# Arduino_S3v3_R2_ftdi.net
KiCad netlist of a schematic drawn in EAGLE
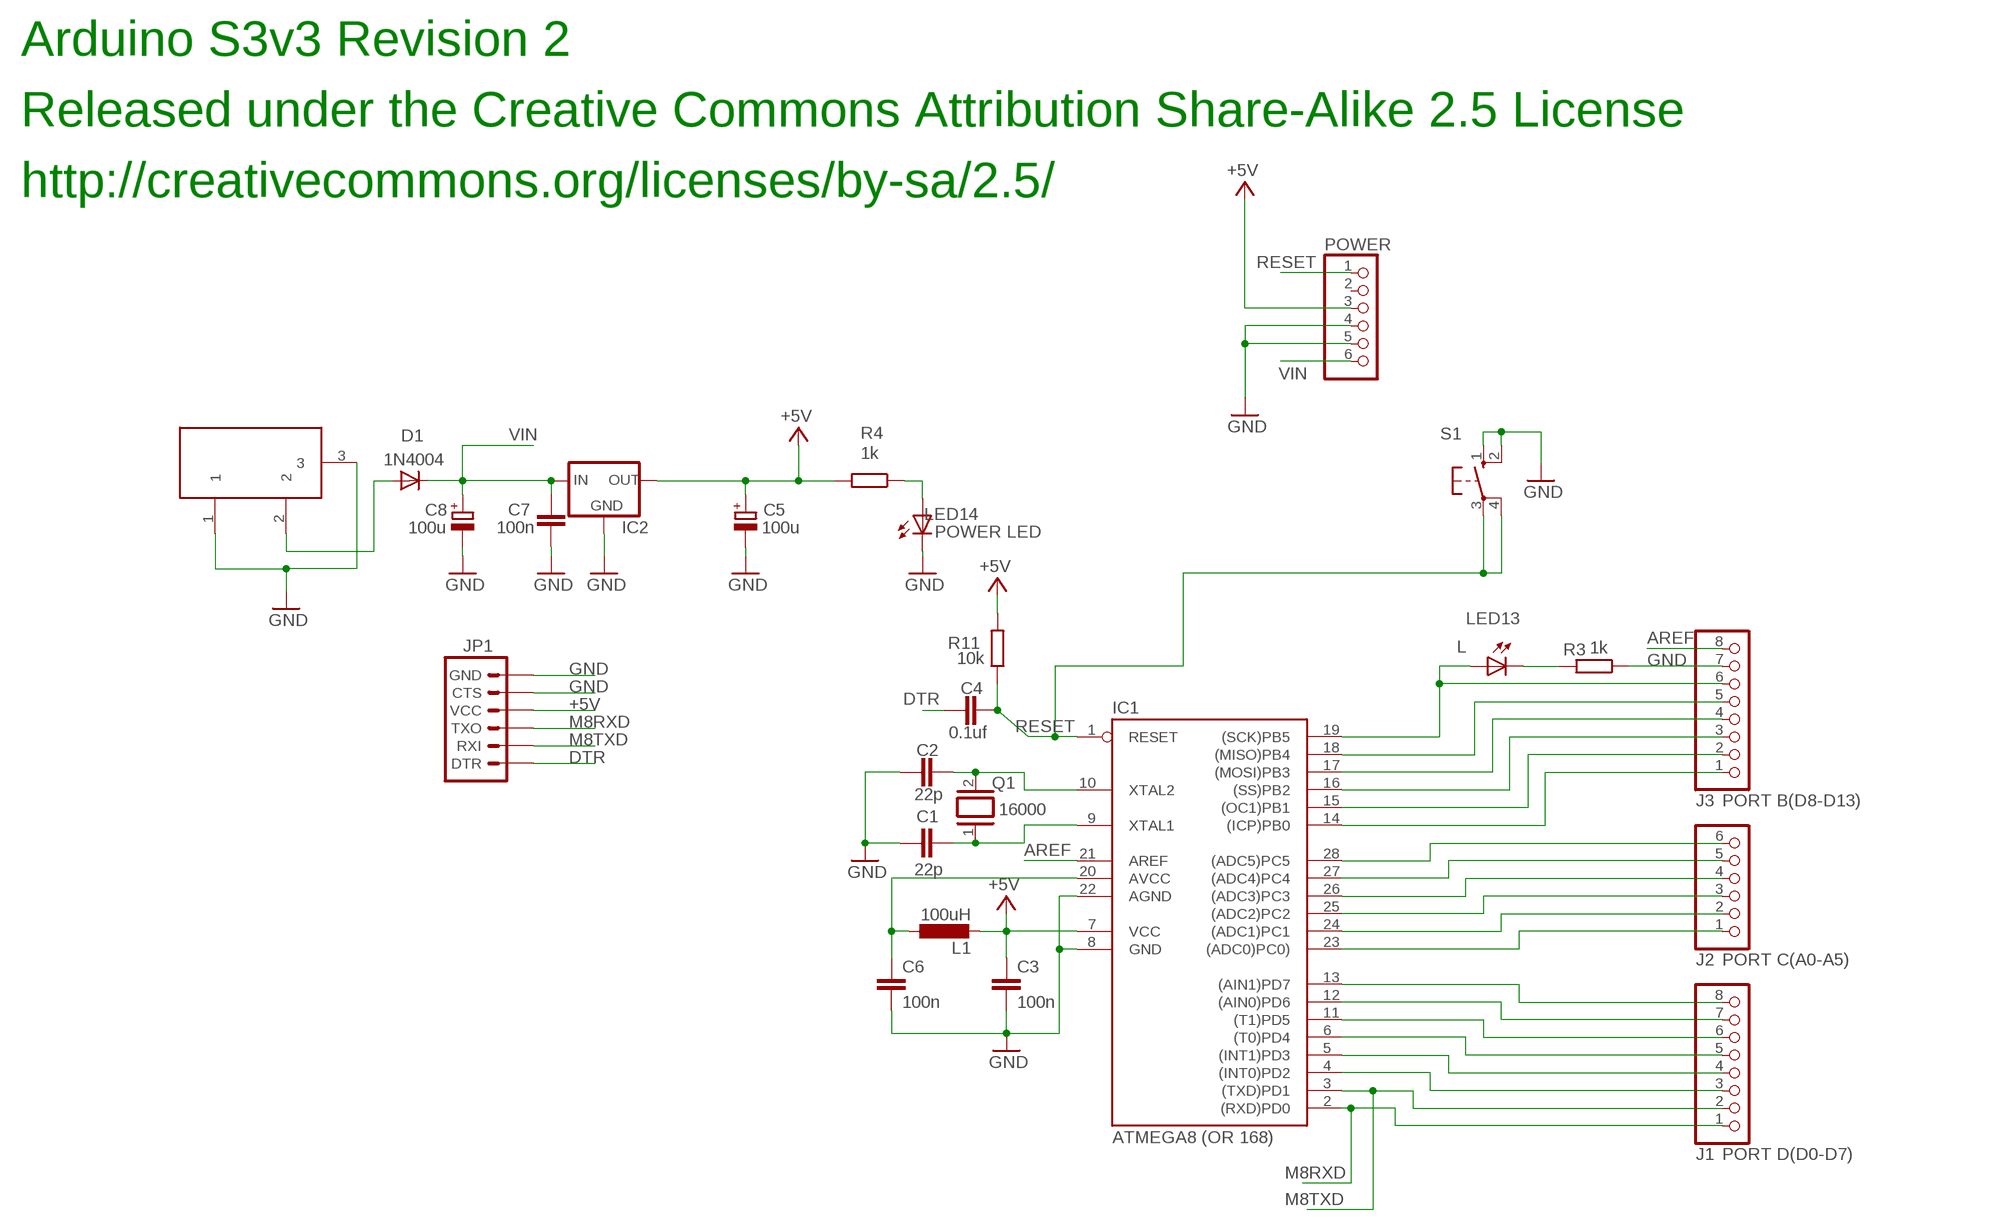
[diagram p0: schematic, sheet 1]

(export (version "E")
  (design (tool "Eeschema 10.0.6"))
  (components
    (comp (ref "C1")
      (value "22p")
      (footprint "eagle-import:C050-025X075")
      (libsource (lib "eagle-import") (part "C-EU050-025X075"))
    )
    (comp (ref "C2")
      (value "22p")
      (footprint "eagle-import:C050-025X075")
      (libsource (lib "eagle-import") (part "C-EU050-025X075"))
    )
    (comp (ref "C3")
      (value "100n")
      (footprint "eagle-import:C050-025X075")
      (libsource (lib "eagle-import") (part "C-EU050-025X075"))
    )
    (comp (ref "C4")
      (value "0.1uf")
      (footprint "eagle-import:C050-025X075")
      (libsource (lib "eagle-import") (part "C-EU050-025X075"))
    )
    (comp (ref "C5")
      (value "100u")
      (footprint "eagle-import:E3,5-8")
      (libsource (lib "eagle-import") (part "CPOL-EUE3.5-8"))
    )
    (comp (ref "C6")
      (value "100n")
      (footprint "eagle-import:C050-025X075")
      (libsource (lib "eagle-import") (part "C-EU050-025X075"))
    )
    (comp (ref "C7")
      (value "100n")
      (footprint "eagle-import:C050-025X075")
      (libsource (lib "eagle-import") (part "C-EU050-025X075"))
    )
    (comp (ref "C8")
      (value "100u")
      (footprint "eagle-import:E3,5-8")
      (libsource (lib "eagle-import") (part "CPOL-EUE3.5-8"))
    )
    (comp (ref "D1")
      (value "1N4004")
      (footprint "eagle-import:DO41-10")
      (libsource (lib "eagle-import") (part "1N4004"))
    )
    (comp (ref "DC1")
      (value "DC21MMX")
      (footprint "eagle-import:DC-21MM")
      (libsource (lib "eagle-import") (part "DC21MMX"))
    )
    (comp (ref "IC1")
      (value "ATMEGA8 (OR 168)")
      (footprint "eagle-import:DIL28-3")
      (libsource (lib "eagle-import") (part "AT90S4433P"))
    )
    (comp (ref "IC2")
      (value "78XXL")
      (footprint "eagle-import:78XXL")
      (libsource (lib "eagle-import") (part "78XXL"))
    )
    (comp (ref "J1")
      (value "PORT D(D0-D7)")
      (footprint "eagle-import:1X08")
      (libsource (lib "eagle-import") (part "PINHD-1X8"))
    )
    (comp (ref "J2")
      (value "PORT C(A0-A5)")
      (footprint "eagle-import:1X06")
      (libsource (lib "eagle-import") (part "PINHD-1X6"))
    )
    (comp (ref "J3")
      (value "PORT B(D8-D13)")
      (footprint "eagle-import:1X08")
      (libsource (lib "eagle-import") (part "PINHD-1X8"))
    )
    (comp (ref "JP1")
      (value "ARDUINO_SERIAL_PROGRAMLONGPADS")
      (footprint "eagle-import:1X06_LONGPADS")
      (libsource (lib "eagle-import") (part "ARDUINO_SERIAL_PROGRAMLONGPADS"))
    )
    (comp (ref "L1")
      (value "100uH")
      (footprint "eagle-import:0207_10@1")
      (libsource (lib "eagle-import") (part "L-EU0207/10"))
    )
    (comp (ref "LED13")
      (value "L")
      (footprint "eagle-import:LED3MM")
      (libsource (lib "eagle-import") (part "LED3MM"))
    )
    (comp (ref "LED14")
      (value "POWER LED")
      (footprint "eagle-import:LED3MM")
      (libsource (lib "eagle-import") (part "LED3MM"))
    )
    (comp (ref "POWER")
      (value "PINHD-1X6")
      (footprint "eagle-import:1X06")
      (libsource (lib "eagle-import") (part "PINHD-1X6"))
    )
    (comp (ref "Q1")
      (value "16000")
      (footprint "eagle-import:Q")
      (libsource (lib "eagle-import") (part "XTAL"))
    )
    (comp (ref "R3")
      (value "1k")
      (footprint "eagle-import:0207_10")
      (libsource (lib "eagle-import") (part "R-EU_0207/10"))
    )
    (comp (ref "R4")
      (value "1k")
      (footprint "eagle-import:0207_10")
      (libsource (lib "eagle-import") (part "R-EU_0207/10"))
    )
    (comp (ref "R11")
      (value "10k")
      (footprint "eagle-import:0207_10")
      (libsource (lib "eagle-import") (part "R-EU_0207/10"))
    )
    (comp (ref "S1")
      (value "10-XX")
      (footprint "eagle-import:B3F-10XX")
      (libsource (lib "eagle-import") (part "10-XX"))
    )
  )
  (nets
    (net (code "1") (name "+5V") (class "Default")
      (node (ref "C3") (pin "1") (pinfunction "1_1") (pintype "passive"))
      (node (ref "C5") (pin "+") (pinfunction "+_+") (pintype "passive"))
      (node (ref "IC1") (pin "7") (pinfunction "VCC_7") (pintype "power_in"))
      (node (ref "IC2") (pin "OUT") (pinfunction "OUT_OUT") (pintype "passive"))
      (node (ref "JP1") (pin "4") (pinfunction "VCC_4") (pintype "passive"))
      (node (ref "L1") (pin "2") (pinfunction "2_2") (pintype "passive"))
      (node (ref "POWER") (pin "3") (pinfunction "3_3") (pintype "passive"))
      (node (ref "R11") (pin "2") (pinfunction "2_2") (pintype "passive"))
      (node (ref "R4") (pin "2") (pinfunction "2_2") (pintype "passive"))
    )
    (net (code "2") (name "/AREF") (class "Default")
      (node (ref "IC1") (pin "21") (pinfunction "AREF_21") (pintype "power_in"))
      (node (ref "J3") (pin "8") (pinfunction "8_8") (pintype "passive"))
    )
    (net (code "3") (name "/DTR") (class "Default")
      (node (ref "C4") (pin "1") (pinfunction "1_1") (pintype "passive"))
      (node (ref "JP1") (pin "1") (pinfunction "DTR_1") (pintype "passive"))
    )
    (net (code "4") (name "/M8RXD") (class "Default")
      (node (ref "IC1") (pin "2") (pinfunction "(RXD)PD0_2") (pintype "bidirectional"))
      (node (ref "J1") (pin "1") (pinfunction "1_1") (pintype "passive"))
      (node (ref "JP1") (pin "3") (pinfunction "TXO_3") (pintype "passive"))
    )
    (net (code "5") (name "/M8TXD") (class "Default")
      (node (ref "IC1") (pin "3") (pinfunction "(TXD)PD1_3") (pintype "bidirectional"))
      (node (ref "J1") (pin "2") (pinfunction "2_2") (pintype "passive"))
      (node (ref "JP1") (pin "2") (pinfunction "RXI_2") (pintype "passive"))
    )
    (net (code "6") (name "/RESET") (class "Default")
      (node (ref "C4") (pin "2") (pinfunction "2_2") (pintype "passive"))
      (node (ref "IC1") (pin "1") (pinfunction "RESET_1") (pintype "input"))
      (node (ref "POWER") (pin "1") (pinfunction "1_1") (pintype "passive"))
      (node (ref "R11") (pin "1") (pinfunction "1_1") (pintype "passive"))
      (node (ref "S1") (pin "3") (pinfunction "P_3") (pintype "passive"))
      (node (ref "S1") (pin "4") (pinfunction "P1_4") (pintype "passive"))
    )
    (net (code "7") (name "/VIN") (class "Default")
      (node (ref "C7") (pin "2") (pinfunction "2_2") (pintype "passive"))
      (node (ref "C8") (pin "+") (pinfunction "+_+") (pintype "passive"))
      (node (ref "D1") (pin "C") (pinfunction "C_C") (pintype "passive"))
      (node (ref "IC2") (pin "IN") (pinfunction "IN_IN") (pintype "input"))
      (node (ref "POWER") (pin "6") (pinfunction "6_6") (pintype "passive"))
    )
    (net (code "8") (name "GND") (class "Default")
      (node (ref "C1") (pin "1") (pinfunction "1_1") (pintype "passive"))
      (node (ref "C2") (pin "1") (pinfunction "1_1") (pintype "passive"))
      (node (ref "C3") (pin "2") (pinfunction "2_2") (pintype "passive"))
      (node (ref "C5") (pin "-") (pinfunction "-_-") (pintype "passive"))
      (node (ref "C6") (pin "2") (pinfunction "2_2") (pintype "passive"))
      (node (ref "C7") (pin "1") (pinfunction "1_1") (pintype "passive"))
      (node (ref "C8") (pin "-") (pinfunction "-_-") (pintype "passive"))
      (node (ref "DC1") (pin "1") (pinfunction "1_1") (pintype "power_in"))
      (node (ref "DC1") (pin "3") (pinfunction "3_3") (pintype "power_in"))
      (node (ref "IC1") (pin "22") (pinfunction "AGND_22") (pintype "power_in"))
      (node (ref "IC1") (pin "8") (pinfunction "GND_8") (pintype "power_in"))
      (node (ref "IC2") (pin "GND") (pinfunction "GND_GND") (pintype "input"))
      (node (ref "J3") (pin "7") (pinfunction "7_7") (pintype "passive"))
      (node (ref "JP1") (pin "5") (pinfunction "CTS_5") (pintype "passive"))
      (node (ref "JP1") (pin "6") (pinfunction "GND_6") (pintype "passive"))
      (node (ref "LED14") (pin "K") (pinfunction "C_K") (pintype "passive"))
      (node (ref "POWER") (pin "4") (pinfunction "4_4") (pintype "passive"))
      (node (ref "POWER") (pin "5") (pinfunction "5_5") (pintype "passive"))
      (node (ref "R3") (pin "1") (pinfunction "1_1") (pintype "passive"))
      (node (ref "S1") (pin "1") (pinfunction "S_1") (pintype "passive"))
      (node (ref "S1") (pin "2") (pinfunction "S1_2") (pintype "passive"))
    )
    (net (code "9") (name "Net-(D1-PadA)") (class "Default")
      (node (ref "D1") (pin "A") (pinfunction "A_A") (pintype "passive"))
      (node (ref "DC1") (pin "2") (pinfunction "2_2") (pintype "power_in"))
    )
    (net (code "10") (name "Net-(IC1-(ADC0)PC0))") (class "Default")
      (node (ref "IC1") (pin "23") (pinfunction "(ADC0)PC0)_23") (pintype "bidirectional"))
      (node (ref "J2") (pin "1") (pinfunction "1_1") (pintype "passive"))
    )
    (net (code "11") (name "Net-(IC1-(ADC1)PC1)") (class "Default")
      (node (ref "IC1") (pin "24") (pinfunction "(ADC1)PC1_24") (pintype "bidirectional"))
      (node (ref "J2") (pin "2") (pinfunction "2_2") (pintype "passive"))
    )
    (net (code "12") (name "Net-(IC1-(ADC2)PC2)") (class "Default")
      (node (ref "IC1") (pin "25") (pinfunction "(ADC2)PC2_25") (pintype "bidirectional"))
      (node (ref "J2") (pin "3") (pinfunction "3_3") (pintype "passive"))
    )
    (net (code "13") (name "Net-(IC1-(ADC3)PC3)") (class "Default")
      (node (ref "IC1") (pin "26") (pinfunction "(ADC3)PC3_26") (pintype "bidirectional"))
      (node (ref "J2") (pin "4") (pinfunction "4_4") (pintype "passive"))
    )
    (net (code "14") (name "Net-(IC1-(ADC4)PC4)") (class "Default")
      (node (ref "IC1") (pin "27") (pinfunction "(ADC4)PC4_27") (pintype "bidirectional"))
      (node (ref "J2") (pin "5") (pinfunction "5_5") (pintype "passive"))
    )
    (net (code "15") (name "Net-(IC1-(ADC5)PC5)") (class "Default")
      (node (ref "IC1") (pin "28") (pinfunction "(ADC5)PC5_28") (pintype "bidirectional"))
      (node (ref "J2") (pin "6") (pinfunction "6_6") (pintype "passive"))
    )
    (net (code "16") (name "Net-(IC1-(AIN0)PD6)") (class "Default")
      (node (ref "IC1") (pin "12") (pinfunction "(AIN0)PD6_12") (pintype "bidirectional"))
      (node (ref "J1") (pin "7") (pinfunction "7_7") (pintype "passive"))
    )
    (net (code "17") (name "Net-(IC1-(AIN1)PD7)") (class "Default")
      (node (ref "IC1") (pin "13") (pinfunction "(AIN1)PD7_13") (pintype "bidirectional"))
      (node (ref "J1") (pin "8") (pinfunction "8_8") (pintype "passive"))
    )
    (net (code "18") (name "Net-(IC1-(ICP)PB0)") (class "Default")
      (node (ref "IC1") (pin "14") (pinfunction "(ICP)PB0_14") (pintype "bidirectional"))
      (node (ref "J3") (pin "1") (pinfunction "1_1") (pintype "passive"))
    )
    (net (code "19") (name "Net-(IC1-(INT0)PD2)") (class "Default")
      (node (ref "IC1") (pin "4") (pinfunction "(INT0)PD2_4") (pintype "bidirectional"))
      (node (ref "J1") (pin "3") (pinfunction "3_3") (pintype "passive"))
    )
    (net (code "20") (name "Net-(IC1-(INT1)PD3)") (class "Default")
      (node (ref "IC1") (pin "5") (pinfunction "(INT1)PD3_5") (pintype "bidirectional"))
      (node (ref "J1") (pin "4") (pinfunction "4_4") (pintype "passive"))
    )
    (net (code "21") (name "Net-(IC1-(MISO)PB4)") (class "Default")
      (node (ref "IC1") (pin "18") (pinfunction "(MISO)PB4_18") (pintype "bidirectional"))
      (node (ref "J3") (pin "5") (pinfunction "5_5") (pintype "passive"))
    )
    (net (code "22") (name "Net-(IC1-(MOSI)PB3)") (class "Default")
      (node (ref "IC1") (pin "17") (pinfunction "(MOSI)PB3_17") (pintype "bidirectional"))
      (node (ref "J3") (pin "4") (pinfunction "4_4") (pintype "passive"))
    )
    (net (code "23") (name "Net-(IC1-(OC1)PB1)") (class "Default")
      (node (ref "IC1") (pin "15") (pinfunction "(OC1)PB1_15") (pintype "bidirectional"))
      (node (ref "J3") (pin "2") (pinfunction "2_2") (pintype "passive"))
    )
    (net (code "24") (name "Net-(IC1-(SCK)PB5)") (class "Default")
      (node (ref "IC1") (pin "19") (pinfunction "(SCK)PB5_19") (pintype "bidirectional"))
      (node (ref "J3") (pin "6") (pinfunction "6_6") (pintype "passive"))
      (node (ref "LED13") (pin "A") (pinfunction "A_A") (pintype "passive"))
    )
    (net (code "25") (name "Net-(IC1-(SS)PB2)") (class "Default")
      (node (ref "IC1") (pin "16") (pinfunction "(SS)PB2_16") (pintype "bidirectional"))
      (node (ref "J3") (pin "3") (pinfunction "3_3") (pintype "passive"))
    )
    (net (code "26") (name "Net-(IC1-(T0)PD4)") (class "Default")
      (node (ref "IC1") (pin "6") (pinfunction "(T0)PD4_6") (pintype "bidirectional"))
      (node (ref "J1") (pin "5") (pinfunction "5_5") (pintype "passive"))
    )
    (net (code "27") (name "Net-(IC1-(T1)PD5)") (class "Default")
      (node (ref "IC1") (pin "11") (pinfunction "(T1)PD5_11") (pintype "bidirectional"))
      (node (ref "J1") (pin "6") (pinfunction "6_6") (pintype "passive"))
    )
    (net (code "28") (name "Net-(IC1-AVCC)") (class "Default")
      (node (ref "C6") (pin "1") (pinfunction "1_1") (pintype "passive"))
      (node (ref "IC1") (pin "20") (pinfunction "AVCC_20") (pintype "power_in"))
      (node (ref "L1") (pin "1") (pinfunction "1_1") (pintype "passive"))
    )
    (net (code "29") (name "Net-(IC1-XTAL1)") (class "Default")
      (node (ref "C1") (pin "2") (pinfunction "2_2") (pintype "passive"))
      (node (ref "IC1") (pin "9") (pinfunction "XTAL1_9") (pintype "bidirectional"))
      (node (ref "Q1") (pin "1") (pinfunction "1_1") (pintype "passive"))
    )
    (net (code "30") (name "Net-(IC1-XTAL2)") (class "Default")
      (node (ref "C2") (pin "2") (pinfunction "2_2") (pintype "passive"))
      (node (ref "IC1") (pin "10") (pinfunction "XTAL2_10") (pintype "bidirectional"))
      (node (ref "Q1") (pin "2") (pinfunction "2_2") (pintype "passive"))
    )
    (net (code "31") (name "Net-(LED13-C)") (class "Default")
      (node (ref "LED13") (pin "K") (pinfunction "C_K") (pintype "passive"))
      (node (ref "R3") (pin "2") (pinfunction "2_2") (pintype "passive"))
    )
    (net (code "32") (name "Net-(LED14-PadA)") (class "Default")
      (node (ref "LED14") (pin "A") (pinfunction "A_A") (pintype "passive"))
      (node (ref "R4") (pin "1") (pinfunction "1_1") (pintype "passive"))
    )
    (net (code "33") (name "unconnected-(POWER-Pad2)") (class "Default")
      (node (ref "POWER") (pin "2") (pinfunction "2_2") (pintype "passive"))
    )
  )
)
